# PCB0M8A3.net
KiCad netlist of a schematic drawn in EAGLE
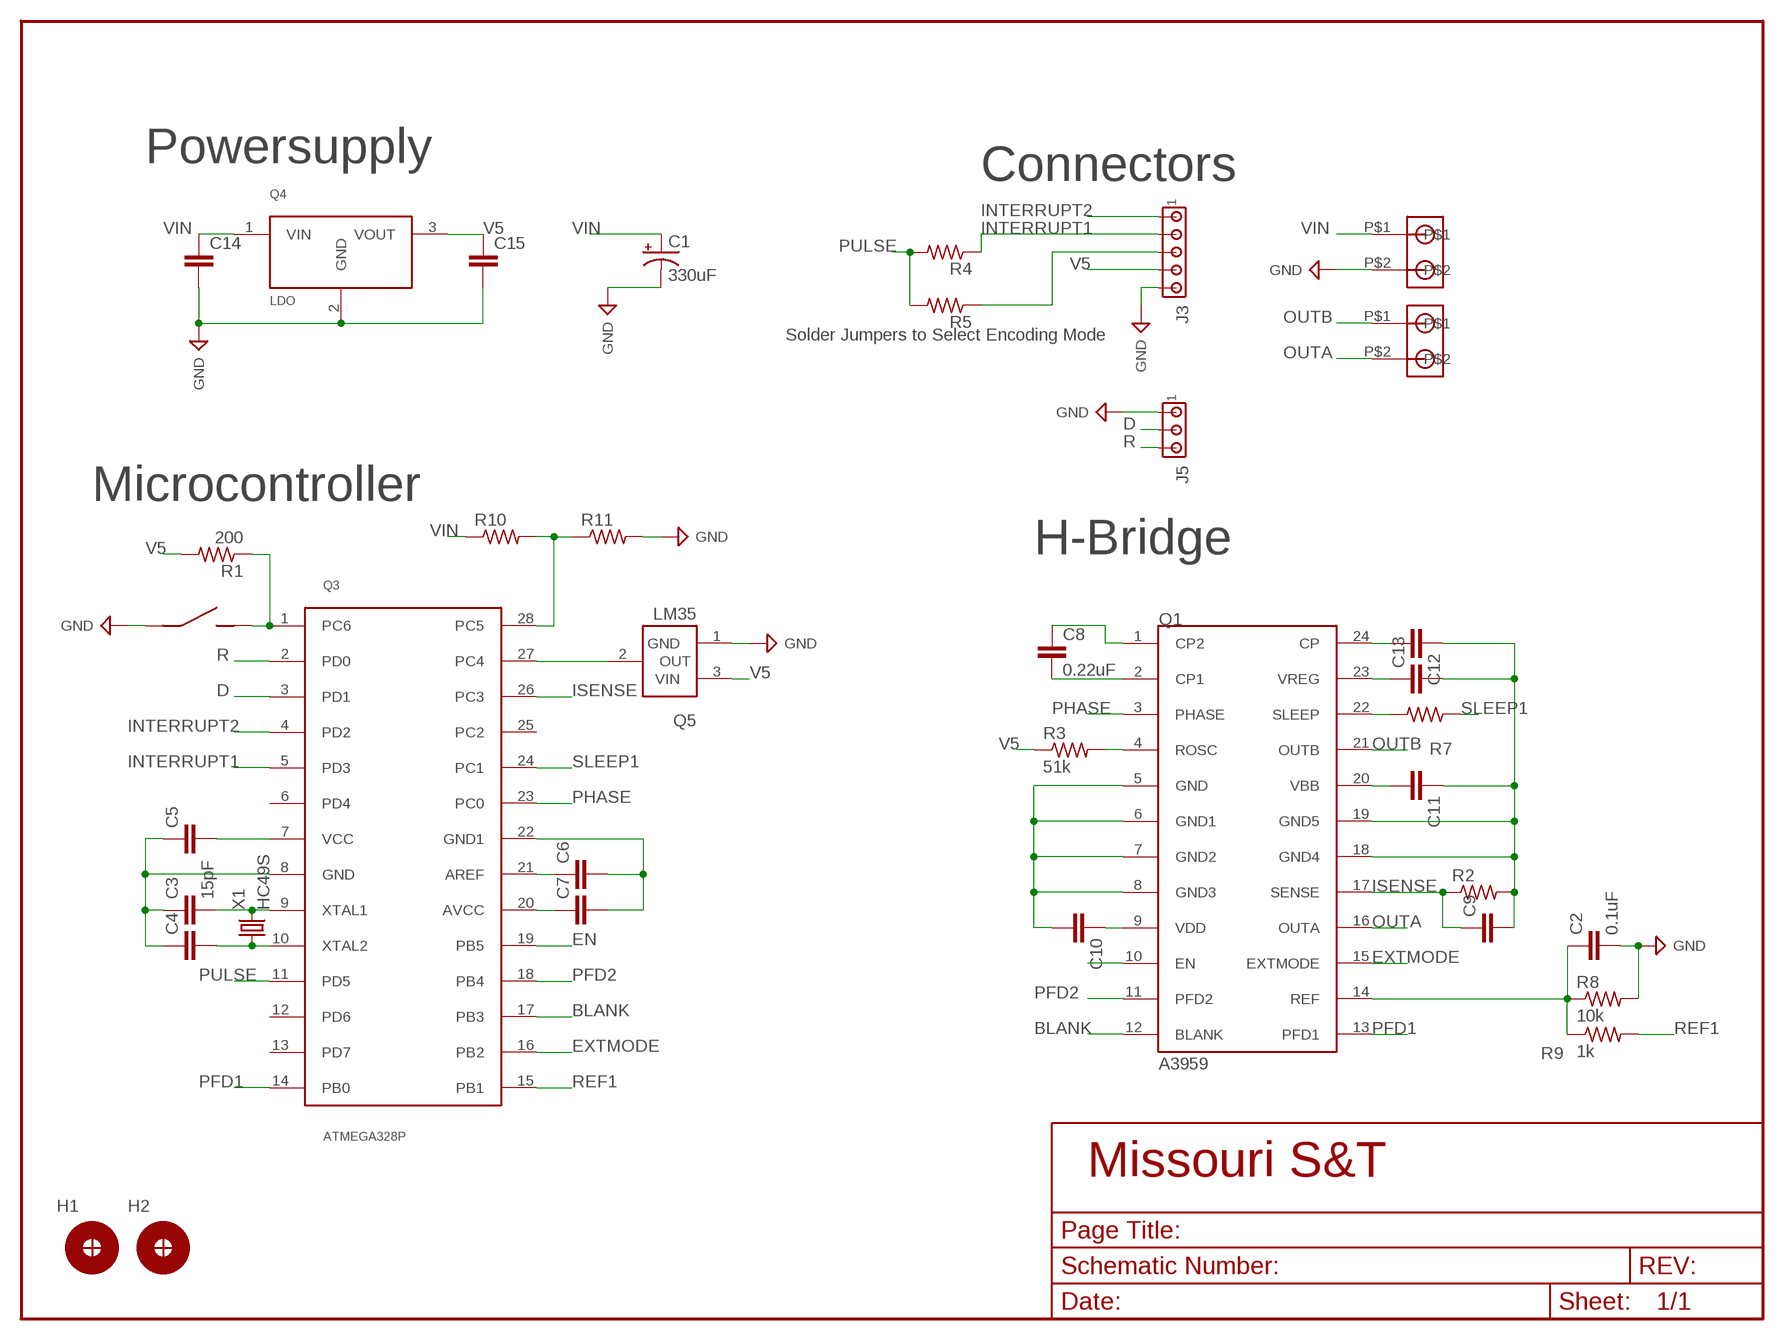
[diagram p0: schematic, sheet 1]

(export (version "E")
  (design (tool "Eeschema 10.0.6"))
  (components
    (comp (ref "C1")
      (value "330uF")
      (footprint "eagle-import:C_8MM")
      (libsource (lib "eagle-import") (part "C_POL8MM"))
    )
    (comp (ref "C2")
      (value "0.1uF")
      (footprint "eagle-import:C_0805")
      (libsource (lib "eagle-import") (part "C_CAP_0805"))
    )
    (comp (ref "C3")
      (value "15pF")
      (footprint "eagle-import:C_0805")
      (libsource (lib "eagle-import") (part "C_CAP_0805"))
    )
    (comp (ref "C4")
      (value "C_CAP_0805")
      (footprint "eagle-import:C_0805")
      (libsource (lib "eagle-import") (part "C_CAP_0805"))
    )
    (comp (ref "C5")
      (value "C_CAP_0805")
      (footprint "eagle-import:C_0805")
      (libsource (lib "eagle-import") (part "C_CAP_0805"))
    )
    (comp (ref "C6")
      (value "C_CAP_0805")
      (footprint "eagle-import:C_0805")
      (libsource (lib "eagle-import") (part "C_CAP_0805"))
    )
    (comp (ref "C7")
      (value "C_CAP_0805")
      (footprint "eagle-import:C_0805")
      (libsource (lib "eagle-import") (part "C_CAP_0805"))
    )
    (comp (ref "C8")
      (value "0.22uF")
      (footprint "eagle-import:C_0805")
      (libsource (lib "eagle-import") (part "C_CAP_0805"))
    )
    (comp (ref "C9")
      (value "C_CAP_0805")
      (footprint "eagle-import:C_0805")
      (libsource (lib "eagle-import") (part "C_CAP_0805"))
    )
    (comp (ref "C10")
      (value "C_CAP_0805")
      (footprint "eagle-import:C_0805")
      (libsource (lib "eagle-import") (part "C_CAP_0805"))
    )
    (comp (ref "C11")
      (value "C_CAP_0805")
      (footprint "eagle-import:C_0805")
      (libsource (lib "eagle-import") (part "C_CAP_0805"))
    )
    (comp (ref "C12")
      (value "C_CAP_0805")
      (footprint "eagle-import:C_0805")
      (libsource (lib "eagle-import") (part "C_CAP_0805"))
    )
    (comp (ref "C13")
      (value "C_CAP_0805")
      (footprint "eagle-import:C_0805")
      (libsource (lib "eagle-import") (part "C_CAP_0805"))
    )
    (comp (ref "C14")
      (value "C_CAP_0805")
      (footprint "eagle-import:C_0805")
      (libsource (lib "eagle-import") (part "C_CAP_0805"))
    )
    (comp (ref "C15")
      (value "C_CAP_0805")
      (footprint "eagle-import:C_0805")
      (libsource (lib "eagle-import") (part "C_CAP_0805"))
    )
    (comp (ref "H1")
      (value "H_MNTHOLE_#4")
      (footprint "eagle-import:H_MNTHOLE_#4")
      (libsource (lib "eagle-import") (part "H_MNTHOLE_#4"))
    )
    (comp (ref "H2")
      (value "H_MNTHOLE_#4")
      (footprint "eagle-import:H_MNTHOLE_#4")
      (libsource (lib "eagle-import") (part "H_MNTHOLE_#4"))
    )
    (comp (ref "J1")
      (value "J_1546074-2282834-2")
      (footprint "eagle-import:J_2.54MM")
      (libsource (lib "eagle-import") (part "J_1546074-2282834-2"))
    )
    (comp (ref "J2")
      (value "J_1546074-2282834-2")
      (footprint "eagle-import:J_2.54MM")
      (libsource (lib "eagle-import") (part "J_1546074-2282834-2"))
    )
    (comp (ref "J3")
      (value "J_MTA5P_100")
      (footprint "eagle-import:J_MTA100_5P")
      (libsource (lib "eagle-import") (part "J_MTA5P_100"))
    )
    (comp (ref "J4")
      (value "J_MC32857")
      (footprint "eagle-import:J_TOGGLE")
      (libsource (lib "eagle-import") (part "J_MC32857"))
    )
    (comp (ref "J5")
      (value "J_MTA3P_100")
      (footprint "eagle-import:J_MTA100_3P")
      (libsource (lib "eagle-import") (part "J_MTA3P_100"))
    )
    (comp (ref "Q1")
      (value "A3959")
      (footprint "eagle-import:DIP24")
      (libsource (lib "eagle-import") (part "Q_A3959"))
    )
    (comp (ref "Q3")
      (value "ATMEGA328P")
      (footprint "eagle-import:DIP28")
      (libsource (lib "eagle-import") (part "Q_ATMEGA328P"))
    )
    (comp (ref "Q4")
      (value "LDO")
      (footprint "eagle-import:TO-220")
      (libsource (lib "eagle-import") (part "Q_LDO"))
    )
    (comp (ref "Q5")
      (value "LM35")
      (footprint "eagle-import:TO-92-3")
      (libsource (lib "eagle-import") (part "Q_LM35"))
    )
    (comp (ref "R1")
      (value "200")
      (footprint "eagle-import:R_0805")
      (libsource (lib "eagle-import") (part "R_RES_0805"))
    )
    (comp (ref "R2")
      (value "R_RES_2010")
      (footprint "eagle-import:R_2010")
      (libsource (lib "eagle-import") (part "R_RES_2010"))
    )
    (comp (ref "R3")
      (value "51k")
      (footprint "eagle-import:R_0805")
      (libsource (lib "eagle-import") (part "R_RES_0805"))
    )
    (comp (ref "R4")
      (value "R_RES_0603")
      (footprint "eagle-import:R_0603")
      (libsource (lib "eagle-import") (part "R_RES_0603"))
    )
    (comp (ref "R5")
      (value "R_RES_0603")
      (footprint "eagle-import:R_0603")
      (libsource (lib "eagle-import") (part "R_RES_0603"))
    )
    (comp (ref "R7")
      (value "R_1/4WL")
      (footprint "eagle-import:R_1_4WL")
      (libsource (lib "eagle-import") (part "R_1/4WL"))
    )
    (comp (ref "R8")
      (value "10k")
      (footprint "eagle-import:R_0805")
      (libsource (lib "eagle-import") (part "R_RES_0805"))
    )
    (comp (ref "R9")
      (value "1k")
      (footprint "eagle-import:R_0805")
      (libsource (lib "eagle-import") (part "R_RES_0805"))
    )
    (comp (ref "R10")
      (value "R_RES_0805")
      (footprint "eagle-import:R_0805")
      (libsource (lib "eagle-import") (part "R_RES_0805"))
    )
    (comp (ref "R11")
      (value "R_RES_0805")
      (footprint "eagle-import:R_0805")
      (libsource (lib "eagle-import") (part "R_RES_0805"))
    )
    (comp (ref "X1")
      (value "HC49S")
      (footprint "eagle-import:HC-49")
      (libsource (lib "eagle-import") (part "X_HC49SCRYSTAL"))
    )
  )
  (nets
    (net (code "1") (name "/BLANK") (class "Default")
      (node (ref "Q1") (pin "12") (pinfunction "BLANK_12") (pintype "bidirectional"))
      (node (ref "Q3") (pin "17") (pinfunction "PB3_17") (pintype "bidirectional"))
    )
    (net (code "2") (name "/D") (class "Default")
      (node (ref "J5") (pin "2") (pinfunction "2_2") (pintype "passive"))
      (node (ref "Q3") (pin "3") (pinfunction "PD1_3") (pintype "bidirectional"))
    )
    (net (code "3") (name "/EN") (class "Default")
      (node (ref "Q1") (pin "10") (pinfunction "EN_10") (pintype "bidirectional"))
      (node (ref "Q3") (pin "19") (pinfunction "PB5_19") (pintype "bidirectional"))
    )
    (net (code "4") (name "/EXTMODE") (class "Default")
      (node (ref "Q1") (pin "15") (pinfunction "EXTMODE_15") (pintype "bidirectional"))
      (node (ref "Q3") (pin "16") (pinfunction "PB2_16") (pintype "bidirectional"))
    )
    (net (code "5") (name "/INTERRUPT1") (class "Default")
      (node (ref "J3") (pin "2") (pinfunction "2_2") (pintype "passive"))
      (node (ref "Q3") (pin "5") (pinfunction "PD3_5") (pintype "bidirectional"))
      (node (ref "R4") (pin "1") (pinfunction "1_1") (pintype "passive"))
    )
    (net (code "6") (name "/INTERRUPT2") (class "Default")
      (node (ref "J3") (pin "1") (pinfunction "1_1") (pintype "passive"))
      (node (ref "Q3") (pin "4") (pinfunction "PD2_4") (pintype "bidirectional"))
    )
    (net (code "7") (name "/ISENSE") (class "Default")
      (node (ref "C9") (pin "1") (pinfunction "1_1") (pintype "passive"))
      (node (ref "Q1") (pin "17") (pinfunction "SENSE_17") (pintype "bidirectional"))
      (node (ref "Q3") (pin "26") (pinfunction "PC3_26") (pintype "bidirectional"))
      (node (ref "R2") (pin "1") (pinfunction "1_1") (pintype "passive"))
    )
    (net (code "8") (name "/OUTA") (class "Default")
      (node (ref "J2") (pin "P$2") (pinfunction "P$2_P$2") (pintype "bidirectional"))
      (node (ref "Q1") (pin "16") (pinfunction "OUTA_16") (pintype "bidirectional"))
    )
    (net (code "9") (name "/OUTB") (class "Default")
      (node (ref "J2") (pin "P$1") (pinfunction "P$1_P$1") (pintype "bidirectional"))
      (node (ref "Q1") (pin "21") (pinfunction "OUTB_21") (pintype "bidirectional"))
    )
    (net (code "10") (name "/PFD1") (class "Default")
      (node (ref "Q1") (pin "13") (pinfunction "PFD1_13") (pintype "bidirectional"))
      (node (ref "Q3") (pin "14") (pinfunction "PB0_14") (pintype "bidirectional"))
    )
    (net (code "11") (name "/PFD2") (class "Default")
      (node (ref "Q1") (pin "11") (pinfunction "PFD2_11") (pintype "bidirectional"))
      (node (ref "Q3") (pin "18") (pinfunction "PB4_18") (pintype "bidirectional"))
    )
    (net (code "12") (name "/PHASE") (class "Default")
      (node (ref "Q1") (pin "3") (pinfunction "PHASE_3") (pintype "bidirectional"))
      (node (ref "Q3") (pin "23") (pinfunction "PC0_23") (pintype "bidirectional"))
    )
    (net (code "13") (name "/PULSE") (class "Default")
      (node (ref "Q3") (pin "11") (pinfunction "PD5_11") (pintype "bidirectional"))
      (node (ref "R4") (pin "2") (pinfunction "2_2") (pintype "passive"))
      (node (ref "R5") (pin "2") (pinfunction "2_2") (pintype "passive"))
    )
    (net (code "14") (name "/R") (class "Default")
      (node (ref "J5") (pin "3") (pinfunction "3_3") (pintype "passive"))
      (node (ref "Q3") (pin "2") (pinfunction "PD0_2") (pintype "bidirectional"))
    )
    (net (code "15") (name "/REF1") (class "Default")
      (node (ref "Q3") (pin "15") (pinfunction "PB1_15") (pintype "bidirectional"))
      (node (ref "R9") (pin "2") (pinfunction "2_2") (pintype "passive"))
    )
    (net (code "16") (name "/SLEEP1") (class "Default")
      (node (ref "Q3") (pin "24") (pinfunction "PC1_24") (pintype "bidirectional"))
      (node (ref "R7") (pin "1") (pinfunction "1_1") (pintype "passive"))
    )
    (net (code "17") (name "/V5") (class "Default")
      (node (ref "C10") (pin "1") (pinfunction "1_1") (pintype "passive"))
      (node (ref "C15") (pin "1") (pinfunction "1_1") (pintype "passive"))
      (node (ref "C5") (pin "2") (pinfunction "2_2") (pintype "passive"))
      (node (ref "C7") (pin "1") (pinfunction "1_1") (pintype "passive"))
      (node (ref "J3") (pin "4") (pinfunction "4_4") (pintype "passive"))
      (node (ref "Q1") (pin "9") (pinfunction "VDD_9") (pintype "bidirectional"))
      (node (ref "Q3") (pin "20") (pinfunction "AVCC_20") (pintype "bidirectional"))
      (node (ref "Q3") (pin "7") (pinfunction "VCC_7") (pintype "bidirectional"))
      (node (ref "Q4") (pin "3") (pinfunction "VOUT_3") (pintype "bidirectional"))
      (node (ref "Q5") (pin "3") (pinfunction "VIN_3") (pintype "bidirectional"))
      (node (ref "R1") (pin "2") (pinfunction "2_2") (pintype "passive"))
      (node (ref "R3") (pin "1") (pinfunction "1_1") (pintype "passive"))
    )
    (net (code "18") (name "/VIN") (class "Default")
      (node (ref "C1") (pin "+") (pinfunction "+_+") (pintype "passive"))
      (node (ref "C11") (pin "2") (pinfunction "2_2") (pintype "passive"))
      (node (ref "C14") (pin "1") (pinfunction "1_1") (pintype "passive"))
      (node (ref "J1") (pin "P$1") (pinfunction "P$1_P$1") (pintype "bidirectional"))
      (node (ref "Q1") (pin "20") (pinfunction "VBB_20") (pintype "bidirectional"))
      (node (ref "Q4") (pin "1") (pinfunction "VIN_1") (pintype "bidirectional"))
      (node (ref "R10") (pin "1") (pinfunction "1_1") (pintype "passive"))
    )
    (net (code "19") (name "Net-(J3-Pad3)") (class "Default")
      (node (ref "J3") (pin "3") (pinfunction "3_3") (pintype "passive"))
      (node (ref "R5") (pin "1") (pinfunction "1_1") (pintype "passive"))
    )
    (net (code "20") (name "Net-(J4-2)") (class "Default")
      (node (ref "J4") (pin "P$2") (pinfunction "2_P$2") (pintype "bidirectional"))
      (node (ref "Q3") (pin "1") (pinfunction "PC6_1") (pintype "bidirectional"))
      (node (ref "R1") (pin "1") (pinfunction "1_1") (pintype "passive"))
    )
    (net (code "21") (name "Net-(Q1-CP)") (class "Default")
      (node (ref "C12") (pin "2") (pinfunction "2_2") (pintype "passive"))
      (node (ref "Q1") (pin "24") (pinfunction "CP_24") (pintype "bidirectional"))
    )
    (net (code "22") (name "Net-(Q1-CP1)") (class "Default")
      (node (ref "C8") (pin "2") (pinfunction "2_2") (pintype "passive"))
      (node (ref "Q1") (pin "2") (pinfunction "CP1_2") (pintype "bidirectional"))
    )
    (net (code "23") (name "Net-(Q1-CP2)") (class "Default")
      (node (ref "C8") (pin "1") (pinfunction "1_1") (pintype "passive"))
      (node (ref "Q1") (pin "1") (pinfunction "CP2_1") (pintype "bidirectional"))
    )
    (net (code "24") (name "Net-(Q1-REF)") (class "Default")
      (node (ref "C2") (pin "1") (pinfunction "1_1") (pintype "passive"))
      (node (ref "Q1") (pin "14") (pinfunction "REF_14") (pintype "bidirectional"))
      (node (ref "R8") (pin "1") (pinfunction "1_1") (pintype "passive"))
      (node (ref "R9") (pin "1") (pinfunction "1_1") (pintype "passive"))
    )
    (net (code "25") (name "Net-(Q1-ROSC)") (class "Default")
      (node (ref "Q1") (pin "4") (pinfunction "ROSC_4") (pintype "bidirectional"))
      (node (ref "R3") (pin "2") (pinfunction "2_2") (pintype "passive"))
    )
    (net (code "26") (name "Net-(Q1-SLEEP)") (class "Default")
      (node (ref "Q1") (pin "22") (pinfunction "SLEEP_22") (pintype "bidirectional"))
      (node (ref "R7") (pin "2") (pinfunction "2_2") (pintype "passive"))
    )
    (net (code "27") (name "Net-(Q1-VREG)") (class "Default")
      (node (ref "C13") (pin "1") (pinfunction "1_1") (pintype "passive"))
      (node (ref "Q1") (pin "23") (pinfunction "VREG_23") (pintype "bidirectional"))
    )
    (net (code "28") (name "Net-(Q3-AREF)") (class "Default")
      (node (ref "C6") (pin "1") (pinfunction "1_1") (pintype "passive"))
      (node (ref "Q3") (pin "21") (pinfunction "AREF_21") (pintype "bidirectional"))
    )
    (net (code "29") (name "Net-(Q3-PC4)") (class "Default")
      (node (ref "Q3") (pin "27") (pinfunction "PC4_27") (pintype "bidirectional"))
      (node (ref "Q5") (pin "2") (pinfunction "OUT_2") (pintype "bidirectional"))
    )
    (net (code "30") (name "Net-(Q3-PC5)") (class "Default")
      (node (ref "Q3") (pin "28") (pinfunction "PC5_28") (pintype "bidirectional"))
      (node (ref "R10") (pin "2") (pinfunction "2_2") (pintype "passive"))
      (node (ref "R11") (pin "1") (pinfunction "1_1") (pintype "passive"))
    )
    (net (code "31") (name "Net-(Q3-XTAL1)") (class "Default")
      (node (ref "C3") (pin "2") (pinfunction "2_2") (pintype "passive"))
      (node (ref "Q3") (pin "9") (pinfunction "XTAL1_9") (pintype "bidirectional"))
      (node (ref "X1") (pin "P$2") (pinfunction "2_P$2") (pintype "passive"))
    )
    (net (code "32") (name "Net-(Q3-XTAL2)") (class "Default")
      (node (ref "C4") (pin "2") (pinfunction "2_2") (pintype "passive"))
      (node (ref "Q3") (pin "10") (pinfunction "XTAL2_10") (pintype "bidirectional"))
      (node (ref "X1") (pin "P$1") (pinfunction "1_P$1") (pintype "passive"))
    )
    (net (code "33") (name "SUP_GND") (class "Default")
      (node (ref "C1") (pin "-") (pinfunction "-_-") (pintype "passive"))
      (node (ref "C10") (pin "2") (pinfunction "2_2") (pintype "passive"))
      (node (ref "C11") (pin "1") (pinfunction "1_1") (pintype "passive"))
      (node (ref "C12") (pin "1") (pinfunction "1_1") (pintype "passive"))
      (node (ref "C13") (pin "2") (pinfunction "2_2") (pintype "passive"))
      (node (ref "C14") (pin "2") (pinfunction "2_2") (pintype "passive"))
      (node (ref "C15") (pin "2") (pinfunction "2_2") (pintype "passive"))
      (node (ref "C2") (pin "2") (pinfunction "2_2") (pintype "passive"))
      (node (ref "C3") (pin "1") (pinfunction "1_1") (pintype "passive"))
      (node (ref "C4") (pin "1") (pinfunction "1_1") (pintype "passive"))
      (node (ref "C5") (pin "1") (pinfunction "1_1") (pintype "passive"))
      (node (ref "C6") (pin "2") (pinfunction "2_2") (pintype "passive"))
      (node (ref "C7") (pin "2") (pinfunction "2_2") (pintype "passive"))
      (node (ref "C9") (pin "2") (pinfunction "2_2") (pintype "passive"))
      (node (ref "J1") (pin "P$2") (pinfunction "P$2_P$2") (pintype "bidirectional"))
      (node (ref "J3") (pin "5") (pinfunction "5_5") (pintype "passive"))
      (node (ref "J4") (pin "P$1") (pinfunction "1_P$1") (pintype "bidirectional"))
      (node (ref "J5") (pin "1") (pinfunction "1_1") (pintype "passive"))
      (node (ref "Q1") (pin "18") (pinfunction "GND4_18") (pintype "bidirectional"))
      (node (ref "Q1") (pin "19") (pinfunction "GND5_19") (pintype "bidirectional"))
      (node (ref "Q1") (pin "5") (pinfunction "GND_5") (pintype "bidirectional"))
      (node (ref "Q1") (pin "6") (pinfunction "GND1_6") (pintype "bidirectional"))
      (node (ref "Q1") (pin "7") (pinfunction "GND2_7") (pintype "bidirectional"))
      (node (ref "Q1") (pin "8") (pinfunction "GND3_8") (pintype "bidirectional"))
      (node (ref "Q3") (pin "22") (pinfunction "GND1_22") (pintype "bidirectional"))
      (node (ref "Q3") (pin "8") (pinfunction "GND_8") (pintype "bidirectional"))
      (node (ref "Q4") (pin "2") (pinfunction "GND_2") (pintype "bidirectional"))
      (node (ref "Q5") (pin "1") (pinfunction "GND_1") (pintype "bidirectional"))
      (node (ref "R11") (pin "2") (pinfunction "2_2") (pintype "passive"))
      (node (ref "R2") (pin "2") (pinfunction "2_2") (pintype "passive"))
      (node (ref "R8") (pin "2") (pinfunction "2_2") (pintype "passive"))
    )
    (net (code "34") (name "unconnected-(H1-Pad1)") (class "Default")
      (node (ref "H1") (pin "1") (pinfunction "1_1") (pintype "passive"))
    )
    (net (code "35") (name "unconnected-(H2-Pad1)") (class "Default")
      (node (ref "H2") (pin "1") (pinfunction "1_1") (pintype "passive"))
    )
    (net (code "36") (name "unconnected-(Q3-PC2-Pad25)") (class "Default")
      (node (ref "Q3") (pin "25") (pinfunction "PC2_25") (pintype "bidirectional"))
    )
    (net (code "37") (name "unconnected-(Q3-PD4-Pad6)") (class "Default")
      (node (ref "Q3") (pin "6") (pinfunction "PD4_6") (pintype "bidirectional"))
    )
    (net (code "38") (name "unconnected-(Q3-PD6-Pad12)") (class "Default")
      (node (ref "Q3") (pin "12") (pinfunction "PD6_12") (pintype "bidirectional"))
    )
    (net (code "39") (name "unconnected-(Q3-PD7-Pad13)") (class "Default")
      (node (ref "Q3") (pin "13") (pinfunction "PD7_13") (pintype "bidirectional"))
    )
  )
)
